# PA_MCU.net
KiCad netlist of a schematic drawn in Altium Designer
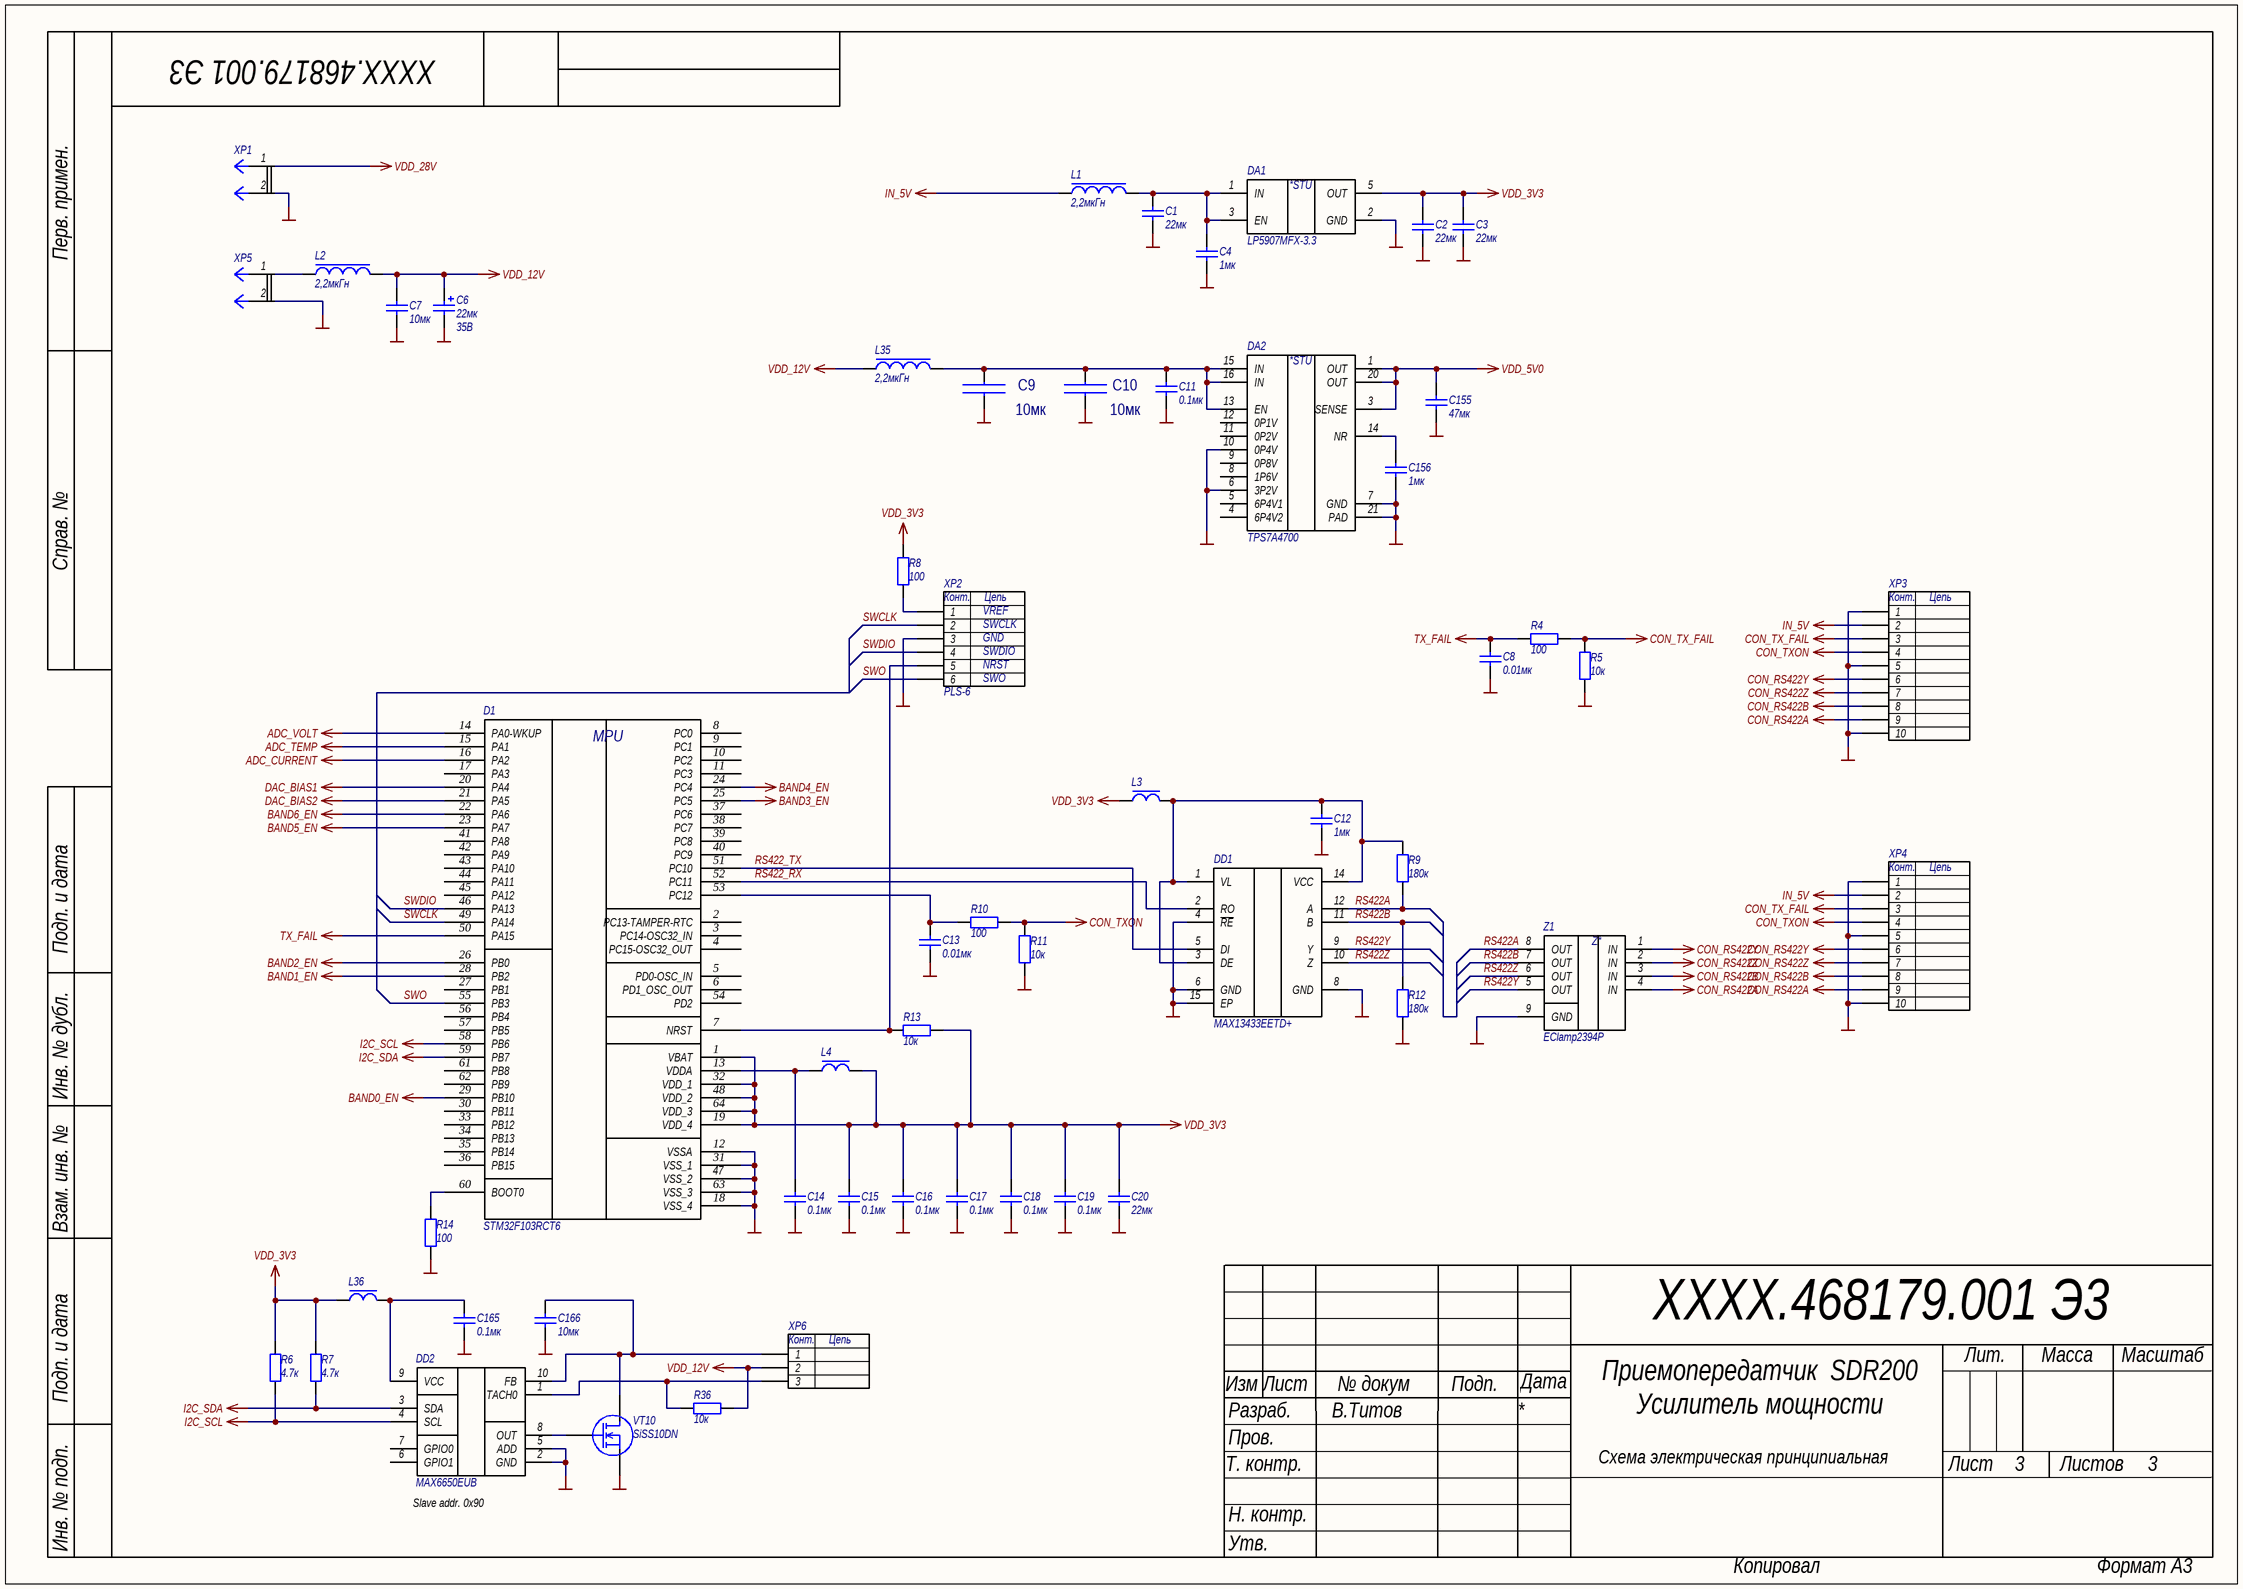
[diagram p0: PA_MCU.SchDoc]

(export (version "E")
  (design (tool "Eeschema 10.0.6"))
  (components
    (comp (ref "C1")
      (value "22мк")
      (footprint "CAPC2012X12L")
      (description "Кер. ЧИП-конденсатор")
      (fields (field (name "MANUFACTURER") "TDK") (field (name "TOLERANCE") "±10%"))
      (libsource (lib "nels_caps") (part "Кер.ЧИП конд. 0805 22мкФ X5R 10% 16В"))
    )
    (comp (ref "C2")
      (value "22мк")
      (footprint "CAPC2012X12L")
      (description "Кер. ЧИП-конденсатор")
      (fields (field (name "MANUFACTURER") "TDK") (field (name "TOLERANCE") "±10%"))
      (libsource (lib "nels_caps") (part "Кер.ЧИП конд. 0805 22мкФ X5R 10% 16В"))
    )
    (comp (ref "C3")
      (value "22мк")
      (footprint "CAPC2012X12L")
      (description "Кер. ЧИП-конденсатор")
      (fields (field (name "MANUFACTURER") "TDK") (field (name "TOLERANCE") "±10%"))
      (libsource (lib "nels_caps") (part "Кер.ЧИП конд. 0805 22мкФ X5R 10% 16В"))
    )
    (comp (ref "C4")
      (value "1мк")
      (footprint "CAPC1005X06N")
      (description "Кер. ЧИП-конденсатор")
      (fields (field (name "TOLERANCE") "±10%"))
      (libsource (lib "nels_caps") (part "Кер.ЧИП конд. 0402 1мкФ X5R 10%, 10В"))
    )
    (comp (ref "C6")
      (value "22мк")
      (footprint "CAPMP7343X28L")
      (description "Тант. ЧИП-конденсатор")
      (fields
        (field (name "TOLERANCE") "±20%")
        (field (name "POWER/VOLTAGE") "35В")
        (field (name "PUBLISHER") "Altium Limited")
      )
      (libsource (lib "nels_caps") (part "Конденсатор танталовый SMD D case 22мкФ ±20% 35B"))
    )
    (comp (ref "C7")
      (value "10мк")
      (footprint "CAPC3225X27L")
      (description "Кер. ЧИП-конденсатор")
      (fields (field (name "MANUFACTURER") "Murata") (field (name "TOLERANCE") "±20%"))
      (libsource (lib "nels_caps") (part "Кер.ЧИП конд. 1210 10мкФ X5R 20% 50В"))
    )
    (comp (ref "C8")
      (value "0.01мк")
      (footprint "CAPC1005X06N")
      (description "Кер. ЧИП-конденсатор")
      (fields (field (name "TOLERANCE") "±20%"))
      (libsource (lib "nels_caps") (part "Кер.ЧИП конд. 0402 0.01мкФ X7R 10%, 50В"))
    )
    (comp (ref "C9")
      (value "CC1206KKX7R8BB106")
      (footprint "CAPC3216X12L")
      (description "ЧИП конденсатор")
      (fields
        (field (name "MANUFACTURER") "Yageo")
        (field (name "TOLERANCE") "10%")
        (field (name "NOMINAL") "10мк")
      )
      (libsource (lib "Database_Gost") (part "Capacitor const"))
    )
    (comp (ref "C10")
      (value "CC0805KKX5R8BB106")
      (footprint "CAPC2012X09L")
      (description "ЧИП конденсатор")
      (fields
        (field (name "MANUFACTURER") "Yageo")
        (field (name "TOLERANCE") "0,1")
        (field (name "NOMINAL") "10мк")
      )
      (libsource (lib "Database_Gost") (part "Capacitor const"))
    )
    (comp (ref "C11")
      (value "0.1мк")
      (footprint "CAPC1005X06N")
      (description "Кер. ЧИП-конденсатор")
      (fields (field (name "TOLERANCE") "±10%"))
      (libsource (lib "nels") (part "Кер.ЧИП конд. 0402 0.1мкФ X7R 10%, 16В"))
    )
    (comp (ref "C12")
      (value "1мк")
      (footprint "CAPC1005X06N")
      (description "Кер. ЧИП-конденсатор")
      (fields (field (name "TOLERANCE") "±10%"))
      (libsource (lib "nels_caps") (part "Кер.ЧИП конд. 0402 1мкФ X5R 10%, 10В"))
    )
    (comp (ref "C13")
      (value "0.01мк")
      (footprint "CAPC1005X06N")
      (description "Кер. ЧИП-конденсатор")
      (fields (field (name "TOLERANCE") "±20%"))
      (libsource (lib "nels_caps") (part "Кер.ЧИП конд. 0402 0.01мкФ X7R 10%, 50В"))
    )
    (comp (ref "C14")
      (value "0.1мк")
      (footprint "CAPC1005X06N")
      (description "Кер. ЧИП-конденсатор")
      (fields (field (name "TOLERANCE") "±10%"))
      (libsource (lib "nels") (part "Кер.ЧИП конд. 0402 0.1мкФ X7R 10%, 16В"))
    )
    (comp (ref "C15")
      (value "0.1мк")
      (footprint "CAPC1005X06N")
      (description "Кер. ЧИП-конденсатор")
      (fields (field (name "TOLERANCE") "±10%"))
      (libsource (lib "nels") (part "Кер.ЧИП конд. 0402 0.1мкФ X7R 10%, 16В"))
    )
    (comp (ref "C16")
      (value "0.1мк")
      (footprint "CAPC1005X06N")
      (description "Кер. ЧИП-конденсатор")
      (fields (field (name "TOLERANCE") "±10%"))
      (libsource (lib "nels") (part "Кер.ЧИП конд. 0402 0.1мкФ X7R 10%, 16В"))
    )
    (comp (ref "C17")
      (value "0.1мк")
      (footprint "CAPC1005X06N")
      (description "Кер. ЧИП-конденсатор")
      (fields (field (name "TOLERANCE") "±10%"))
      (libsource (lib "nels") (part "Кер.ЧИП конд. 0402 0.1мкФ X7R 10%, 16В"))
    )
    (comp (ref "C18")
      (value "0.1мк")
      (footprint "CAPC1005X06N")
      (description "Кер. ЧИП-конденсатор")
      (fields (field (name "TOLERANCE") "±10%"))
      (libsource (lib "nels") (part "Кер.ЧИП конд. 0402 0.1мкФ X7R 10%, 16В"))
    )
    (comp (ref "C19")
      (value "0.1мк")
      (footprint "CAPC1005X06N")
      (description "Кер. ЧИП-конденсатор")
      (fields (field (name "TOLERANCE") "±10%"))
      (libsource (lib "nels") (part "Кер.ЧИП конд. 0402 0.1мкФ X7R 10%, 16В"))
    )
    (comp (ref "C20")
      (value "22мк")
      (footprint "CAPC2012X12L")
      (description "Кер. ЧИП-конденсатор")
      (fields (field (name "MANUFACTURER") "TDK") (field (name "TOLERANCE") "±10%"))
      (libsource (lib "nels_caps") (part "Кер.ЧИП конд. 0805 22мкФ X5R 10% 16В"))
    )
    (comp (ref "C155")
      (value "47мк")
      (footprint "CAPC2012X12L")
      (description "Кер. ЧИП-конденсатор")
      (fields (field (name "MANUFACTURER") "Murata") (field (name "TOLERANCE") "±20%"))
      (libsource (lib "nels_caps") (part "Кер.ЧИП конд. 0805 47мкФ X5R 20% 10В"))
    )
    (comp (ref "C156")
      (value "1мк")
      (footprint "CAPC1005X06N")
      (description "Кер. ЧИП-конденсатор")
      (fields (field (name "TOLERANCE") "±10%"))
      (libsource (lib "nels_caps") (part "Кер.ЧИП конд. 0402 1мкФ X5R 10%, 10В"))
    )
    (comp (ref "C165")
      (value "0.1мк")
      (footprint "CAPC1005X06N")
      (description "Кер. ЧИП-конденсатор")
      (fields (field (name "TOLERANCE") "±10%"))
      (libsource (lib "nels") (part "Кер.ЧИП конд. 0402 0.1мкФ X7R 10%, 16В"))
    )
    (comp (ref "C166")
      (value "10мк")
      (footprint "CAPC3225X27L")
      (description "Кер. ЧИП-конденсатор")
      (fields (field (name "MANUFACTURER") "Murata") (field (name "TOLERANCE") "±20%"))
      (libsource (lib "nels_caps") (part "Кер.ЧИП конд. 1210 10мкФ X5R 20% 50В"))
    )
    (comp (ref "D1")
      (value "STM32F103RCT6")
      (footprint "QFP50P1200X1200X160-64N")
      (fields (field (name "MANUFACTURER") "STMicroelectronics"))
      (libsource (lib "nels_chip") (part "Микросхема STM32F103RCT6"))
    )
    (comp (ref "DA1")
      (value "LP5907MFX-3.3")
      (footprint "SOT23-5AM")
      (description "250-mA Ultra-Low-Noise, Low-IQ LDO")
      (fields (field (name "MANUFACTURER") "TI"))
      (libsource (lib "nels_chip") (part "Микросхема LP5907MFX-3.3"))
    )
    (comp (ref "DA2")
      (value "TPS7A4700")
      (footprint "QFN65P500X500X100_HS-21L")
      (description "36-V, 1-A, 4-µVRMS, RF LDO Voltage Regulator")
      (fields (field (name "MANUFACTURER") "TI"))
      (libsource (lib "nels_chip") (part "Микросхема TPS7A4700RGW"))
    )
    (comp (ref "DD1")
      (value "MAX13433EETD+")
      (footprint "SON40P300X80_HS-15L")
      (description "RS-422 Transceivers with Low-Voltage Logic Interface 16M")
      (fields (field (name "MANUFACTURER") "Maxim"))
      (libsource (lib "nels_chip") (part "Микросхема MAX13433EETD+"))
    )
    (comp (ref "DD2")
      (value "MAX6650EUB")
      (footprint "SOP64P600X175-16N")
      (description "Fan-Speed Regulators and Monitors with SMBus/I2C-Compatible Interface")
      (fields (field (name "MANUFACTURER") "Maxim"))
      (libsource (lib "nels_chip") (part "Микросхема MAX6650EUB"))
    )
    (comp (ref "L1")
      (value "2,2мкГн")
      (footprint "CSAB0420")
      (description "Molding Power Choke")
      (fields
        (field (name "MANUFACTURER") "Vishay")
        (field (name "MANUFACTURERPARTNUMBER") "IHLP1616ABER1R0M11")
      )
      (libsource (lib "nels_ind") (part "ЧИП индуктивность CSAB0420-2R2M"))
    )
    (comp (ref "L2")
      (value "2,2мкГн")
      (footprint "CSAB0420")
      (description "Molding Power Choke")
      (fields
        (field (name "MANUFACTURER") "Vishay")
        (field (name "MANUFACTURERPARTNUMBER") "IHLP1616ABER1R0M11")
      )
      (libsource (lib "nels_ind") (part "ЧИП индуктивность CSAB0420-2R2M"))
    )
    (comp (ref "L3")
      (value "BLM18PG121SN1D")
      (footprint "INDC1608X08L")
      (description "SMD EMI Suppression Filter EMIFIL")
      (fields (field (name "MANUFACTURER") "Murata"))
      (libsource (lib "nels_ind") (part "ЧИП дроссель 0603 BLM18PG121SN1D"))
    )
    (comp (ref "L4")
      (value "BLM18PG121SN1D")
      (footprint "INDC1608X08L")
      (description "SMD EMI Suppression Filter EMIFIL")
      (fields (field (name "MANUFACTURER") "Murata"))
      (libsource (lib "nels_ind") (part "ЧИП дроссель 0603 BLM18PG121SN1D"))
    )
    (comp (ref "L35")
      (value "2,2мкГн")
      (footprint "CSAB0420")
      (description "Molding Power Choke")
      (fields
        (field (name "MANUFACTURER") "Vishay")
        (field (name "MANUFACTURERPARTNUMBER") "IHLP1616ABER1R0M11")
      )
      (libsource (lib "nels_ind") (part "ЧИП индуктивность CSAB0420-2R2M"))
    )
    (comp (ref "L36")
      (value "BLM18PG121SN1D")
      (footprint "INDC1608X08L")
      (description "SMD EMI Suppression Filter EMIFIL")
      (fields (field (name "MANUFACTURER") "Murata"))
      (libsource (lib "nels_ind") (part "ЧИП дроссель 0603 BLM18PG121SN1D"))
    )
    (comp (ref "R4")
      (value "100")
      (footprint "RESC1005X06N")
      (description "ЧИП-резистор")
      (fields (field (name "TOLERANCE") "±5%"))
      (libsource (lib "") (part "Чип резистор 0402 100 Ом, 5%_1"))
    )
    (comp (ref "R5")
      (value "10к")
      (footprint "RESC1005X06N")
      (description "ЧИП-резистор")
      (fields (field (name "TOLERANCE") "±5%"))
      (libsource (lib "") (part "Чип резистор 0402 10 кОм, 5%_1"))
    )
    (comp (ref "R6")
      (value "4.7к")
      (footprint "RESC1005X06N")
      (description "ЧИП-резистор")
      (fields (field (name "TOLERANCE") "±5%"))
      (libsource (lib "nels_res") (part "Чип резистор 0402 4,7 кОм, 5%"))
    )
    (comp (ref "R7")
      (value "4.7к")
      (footprint "RESC1005X06N")
      (description "ЧИП-резистор")
      (fields (field (name "TOLERANCE") "±5%"))
      (libsource (lib "nels_res") (part "Чип резистор 0402 4,7 кОм, 5%"))
    )
    (comp (ref "R8")
      (value "100")
      (footprint "RESC1005X06N")
      (description "ЧИП-резистор")
      (fields (field (name "TOLERANCE") "±5%"))
      (libsource (lib "nels_res") (part "Чип резистор 0402 100 Ом, 5%"))
    )
    (comp (ref "R9")
      (value "180к")
      (footprint "RESC1005X06N")
      (description "ЧИП-резистор")
      (fields (field (name "TOLERANCE") "±5%"))
      (libsource (lib "nels") (part "Чип резистор 0402 180 кОм, 5%"))
    )
    (comp (ref "R10")
      (value "100")
      (footprint "RESC1005X06N")
      (description "ЧИП-резистор")
      (fields (field (name "TOLERANCE") "±5%"))
      (libsource (lib "") (part "Чип резистор 0402 100 Ом, 5%_1"))
    )
    (comp (ref "R11")
      (value "10к")
      (footprint "RESC1005X06N")
      (description "ЧИП-резистор")
      (fields (field (name "TOLERANCE") "±5%"))
      (libsource (lib "") (part "Чип резистор 0402 10 кОм, 5%_1"))
    )
    (comp (ref "R12")
      (value "180к")
      (footprint "RESC1005X06N")
      (description "ЧИП-резистор")
      (fields (field (name "TOLERANCE") "±5%"))
      (libsource (lib "nels") (part "Чип резистор 0402 180 кОм, 5%"))
    )
    (comp (ref "R13")
      (value "10к")
      (footprint "RESC1005X06N")
      (description "ЧИП-резистор")
      (fields (field (name "TOLERANCE") "±5%"))
      (libsource (lib "nels_res") (part "Чип резистор 0402 10 кОм, 5%"))
    )
    (comp (ref "R14")
      (value "100")
      (footprint "RESC1005X06N")
      (description "ЧИП-резистор")
      (fields (field (name "TOLERANCE") "±5%"))
      (libsource (lib "nels_res") (part "Чип резистор 0402 100 Ом, 5%"))
    )
    (comp (ref "R36")
      (value "10к")
      (footprint "RESC1005X06N")
      (description "ЧИП-резистор")
      (fields (field (name "TOLERANCE") "±5%"))
      (libsource (lib "nels_res") (part "Чип резистор 0402 10 кОм, 5%"))
    )
    (comp (ref "VT10")
      (value "SiSS10DN")
      (footprint "PowerPAK_1212-8W")
      (description "N-Channel 40 V (D-S) MOSFET")
      (libsource (lib "nels_other") (part "ЧИП транзистор SiSS10DN"))
    )
    (comp (ref "XP1")
      (value "XT60-F")
      (footprint "XT60-F")
      (description "AMASS XT60-F")
      (libsource (lib "nels_conn") (part "Соединитель XT60-F"))
    )
    (comp (ref "XP2")
      (value "PLS-6")
      (footprint "HDR1X6")
      (description "Вилка штыревая 2.54мм 1x6 прямая тип1")
      (fields (field (name "PUBLISHER") "Altium Limited"))
      (libsource (lib "nels_conn") (part "Соединитель PLS-6"))
    )
    (comp (ref "XP3")
      (value "FH12-10S-0.5SVA")
      (footprint "FH12-10S-0.5SH")
      (description "0.5mm  Pitch FPC/FFC Connector FH12 Series")
      (fields (field (name "MANUFACTURER") "Hirose"))
      (libsource (lib "nels_conn") (part "Соединитель FH12-10S-0.5SVA"))
    )
    (comp (ref "XP4")
      (value "FH12-10S-0.5SVA")
      (footprint "FH12-10S-0.5SH")
      (description "0.5mm  Pitch FPC/FFC Connector FH12 Series")
      (fields (field (name "MANUFACTURER") "Hirose"))
      (libsource (lib "nels_conn") (part "Соединитель FH12-10S-0.5SVA"))
    )
    (comp (ref "XP5")
      (value "XT30UPB-M")
      (footprint "XT30UPB-M")
      (description "AMASS XT30UPB-M  5 mm")
      (libsource (lib "nels_conn") (part "Соединитель XT30UPB-M"))
    )
    (comp (ref "XP6")
      (value "22232031")
      (footprint "22232031")
      (description "Molex 2,54 мм pitch-3")
      (fields (field (name "MANUFACTURER") "Connfly"))
      (libsource (lib "nels_conn") (part "Соединитель 22232031"))
    )
    (comp (ref "Z1")
      (value "EClamp2394P")
      (footprint "SON50P160X65_HS-9N")
      (description "ESD/EMI Protection  for Color LCD Interfaces")
      (fields (field (name "MANUFACTURER") "SEMTECH"))
      (libsource (lib "nels_other") (part "Фильтр EMI EClamp2394P"))
    )
  )
  (nets
    (net (code "1") (name "/RS422A") (class "Default")
      (node (ref "DD1") (pin "12") (pinfunction "A_12") (pintype "passive"))
      (node (ref "R9") (pin "1") (pinfunction "1_1") (pintype "passive"))
      (node (ref "Z1") (pin "8") (pinfunction "OUT_8") (pintype "passive"))
    )
    (net (code "2") (name "/RS422B") (class "Default")
      (node (ref "DD1") (pin "11") (pinfunction "B_11") (pintype "passive"))
      (node (ref "R12") (pin "2") (pinfunction "2_2") (pintype "passive"))
      (node (ref "Z1") (pin "7") (pinfunction "OUT_7") (pintype "passive"))
    )
    (net (code "3") (name "/RS422Y") (class "Default")
      (node (ref "DD1") (pin "9") (pinfunction "Y_9") (pintype "passive"))
      (node (ref "Z1") (pin "5") (pinfunction "OUT_5") (pintype "passive"))
    )
    (net (code "4") (name "/RS422Z") (class "Default")
      (node (ref "DD1") (pin "10") (pinfunction "Z_10") (pintype "passive"))
      (node (ref "Z1") (pin "6") (pinfunction "OUT_6") (pintype "passive"))
    )
    (net (code "5") (name "/RS422_RX") (class "Default")
      (node (ref "D1") (pin "52") (pinfunction "PC11_52") (pintype "passive"))
      (node (ref "DD1") (pin "2") (pinfunction "RO_2") (pintype "passive"))
    )
    (net (code "6") (name "/RS422_TX") (class "Default")
      (node (ref "D1") (pin "51") (pinfunction "PC10_51") (pintype "passive"))
      (node (ref "DD1") (pin "5") (pinfunction "DI_5") (pintype "passive"))
    )
    (net (code "7") (name "/SWCLK") (class "Default")
      (node (ref "D1") (pin "49") (pinfunction "PA14_49") (pintype "passive"))
      (node (ref "XP2") (pin "2") (pinfunction "2_2") (pintype "passive"))
    )
    (net (code "8") (name "/SWDIO") (class "Default")
      (node (ref "D1") (pin "46") (pinfunction "PA13_46") (pintype "passive"))
      (node (ref "XP2") (pin "4") (pinfunction "4_4") (pintype "passive"))
    )
    (net (code "9") (name "/SWO") (class "Default")
      (node (ref "D1") (pin "55") (pinfunction "PB3_55") (pintype "passive"))
      (node (ref "XP2") (pin "6") (pinfunction "6_6") (pintype "passive"))
    )
    (net (code "10") (name "ADC_CURRENT") (class "Default")
      (node (ref "D1") (pin "16") (pinfunction "PA2_16") (pintype "passive"))
    )
    (net (code "11") (name "ADC_TEMP") (class "Default")
      (node (ref "D1") (pin "15") (pinfunction "PA1_15") (pintype "passive"))
    )
    (net (code "12") (name "ADC_VOLT") (class "Default")
      (node (ref "D1") (pin "14") (pinfunction "PA0-WKUP_14") (pintype "passive"))
    )
    (net (code "13") (name "BAND0_EN") (class "Default")
      (node (ref "D1") (pin "29") (pinfunction "PB10_29") (pintype "passive"))
    )
    (net (code "14") (name "BAND1_EN") (class "Default")
      (node (ref "D1") (pin "28") (pinfunction "PB2_28") (pintype "passive"))
    )
    (net (code "15") (name "BAND2_EN") (class "Default")
      (node (ref "D1") (pin "26") (pinfunction "PB0_26") (pintype "passive"))
    )
    (net (code "16") (name "BAND3_EN") (class "Default")
      (node (ref "D1") (pin "25") (pinfunction "PC5_25") (pintype "passive"))
    )
    (net (code "17") (name "BAND4_EN") (class "Default")
      (node (ref "D1") (pin "24") (pinfunction "PC4_24") (pintype "passive"))
    )
    (net (code "18") (name "BAND5_EN") (class "Default")
      (node (ref "D1") (pin "23") (pinfunction "PA7_23") (pintype "passive"))
    )
    (net (code "19") (name "BAND6_EN") (class "Default")
      (node (ref "D1") (pin "22") (pinfunction "PA6_22") (pintype "passive"))
    )
    (net (code "20") (name "CON_RS422A") (class "Default")
      (node (ref "XP3") (pin "9") (pinfunction "9_9") (pintype "passive"))
      (node (ref "XP4") (pin "9") (pinfunction "9_9") (pintype "passive"))
      (node (ref "Z1") (pin "4") (pinfunction "IN_4") (pintype "passive"))
    )
    (net (code "21") (name "CON_RS422B") (class "Default")
      (node (ref "XP3") (pin "8") (pinfunction "8_8") (pintype "passive"))
      (node (ref "XP4") (pin "8") (pinfunction "8_8") (pintype "passive"))
      (node (ref "Z1") (pin "3") (pinfunction "IN_3") (pintype "passive"))
    )
    (net (code "22") (name "CON_RS422Y") (class "Default")
      (node (ref "XP3") (pin "6") (pinfunction "6_6") (pintype "passive"))
      (node (ref "XP4") (pin "6") (pinfunction "6_6") (pintype "passive"))
      (node (ref "Z1") (pin "1") (pinfunction "IN_1") (pintype "passive"))
    )
    (net (code "23") (name "CON_RS422Z") (class "Default")
      (node (ref "XP3") (pin "7") (pinfunction "7_7") (pintype "passive"))
      (node (ref "XP4") (pin "7") (pinfunction "7_7") (pintype "passive"))
      (node (ref "Z1") (pin "2") (pinfunction "IN_2") (pintype "passive"))
    )
    (net (code "24") (name "CON_TXON") (class "Default")
      (node (ref "R10") (pin "1") (pinfunction "1_1") (pintype "passive"))
      (node (ref "R11") (pin "1") (pinfunction "1_1") (pintype "passive"))
      (node (ref "XP3") (pin "4") (pinfunction "4_4") (pintype "passive"))
      (node (ref "XP4") (pin "4") (pinfunction "4_4") (pintype "passive"))
    )
    (net (code "25") (name "CON_TX_FAIL") (class "Default")
      (node (ref "R4") (pin "1") (pinfunction "1_1") (pintype "passive"))
      (node (ref "R5") (pin "1") (pinfunction "1_1") (pintype "passive"))
      (node (ref "XP3") (pin "3") (pinfunction "3_3") (pintype "passive"))
      (node (ref "XP4") (pin "3") (pinfunction "3_3") (pintype "passive"))
    )
    (net (code "26") (name "DAC_BIAS1") (class "Default")
      (node (ref "D1") (pin "20") (pinfunction "PA4_20") (pintype "passive"))
    )
    (net (code "27") (name "DAC_BIAS2") (class "Default")
      (node (ref "D1") (pin "21") (pinfunction "PA5_21") (pintype "passive"))
    )
    (net (code "28") (name "GND") (class "Default")
      (node (ref "C1") (pin "1") (pinfunction "1_1") (pintype "passive"))
      (node (ref "C11") (pin "1") (pinfunction "1_1") (pintype "passive"))
      (node (ref "C12") (pin "1") (pinfunction "1_1") (pintype "passive"))
      (node (ref "C13") (pin "1") (pinfunction "1_1") (pintype "passive"))
      (node (ref "C14") (pin "1") (pinfunction "1_1") (pintype "passive"))
      (node (ref "C15") (pin "1") (pinfunction "1_1") (pintype "passive"))
      (node (ref "C155") (pin "1") (pinfunction "1_1") (pintype "passive"))
      (node (ref "C156") (pin "1") (pinfunction "1_1") (pintype "passive"))
      (node (ref "C16") (pin "1") (pinfunction "1_1") (pintype "passive"))
      (node (ref "C165") (pin "1") (pinfunction "1_1") (pintype "passive"))
      (node (ref "C166") (pin "1") (pinfunction "1_1") (pintype "passive"))
      (node (ref "C17") (pin "1") (pinfunction "1_1") (pintype "passive"))
      (node (ref "C18") (pin "1") (pinfunction "1_1") (pintype "passive"))
      (node (ref "C19") (pin "1") (pinfunction "1_1") (pintype "passive"))
      (node (ref "C2") (pin "1") (pinfunction "1_1") (pintype "passive"))
      (node (ref "C20") (pin "1") (pinfunction "1_1") (pintype "passive"))
      (node (ref "C3") (pin "1") (pinfunction "1_1") (pintype "passive"))
      (node (ref "C4") (pin "1") (pinfunction "1_1") (pintype "passive"))
      (node (ref "C6") (pin "1") (pinfunction "1_1") (pintype "passive"))
      (node (ref "C7") (pin "1") (pinfunction "1_1") (pintype "passive"))
      (node (ref "C8") (pin "1") (pinfunction "1_1") (pintype "passive"))
      (node (ref "D1") (pin "12") (pinfunction "VSSA_12") (pintype "passive"))
      (node (ref "D1") (pin "18") (pinfunction "VSS_4_18") (pintype "passive"))
      (node (ref "D1") (pin "31") (pinfunction "VSS_1_31") (pintype "passive"))
      (node (ref "D1") (pin "47") (pinfunction "VSS_2_47") (pintype "passive"))
      (node (ref "D1") (pin "63") (pinfunction "VSS_3_63") (pintype "passive"))
      (node (ref "DA1") (pin "2") (pinfunction "GND_2") (pintype "passive"))
      (node (ref "DA2") (pin "10") (pinfunction "0P4V_10") (pintype "passive"))
      (node (ref "DA2") (pin "21") (pinfunction "PAD_21") (pintype "passive"))
      (node (ref "DA2") (pin "6") (pinfunction "3P2V_6") (pintype "passive"))
      (node (ref "DA2") (pin "7") (pinfunction "GND_7") (pintype "passive"))
      (node (ref "DD1") (pin "15") (pinfunction "EP_15") (pintype "passive"))
      (node (ref "DD1") (pin "4") (pinfunction "~{RE}_4") (pintype "passive"))
      (node (ref "DD1") (pin "6") (pinfunction "GND_6") (pintype "passive"))
      (node (ref "DD1") (pin "8") (pinfunction "GND_8") (pintype "passive"))
      (node (ref "DD2") (pin "2") (pinfunction "GND_2") (pintype "passive"))
      (node (ref "DD2") (pin "5") (pinfunction "ADD_5") (pintype "passive"))
      (node (ref "R11") (pin "2") (pinfunction "2_2") (pintype "passive"))
      (node (ref "R12") (pin "1") (pinfunction "1_1") (pintype "passive"))
      (node (ref "R14") (pin "2") (pinfunction "2_2") (pintype "passive"))
      (node (ref "R5") (pin "2") (pinfunction "2_2") (pintype "passive"))
      (node (ref "VT10") (pin "S") (pinfunction "S_S") (pintype "passive"))
      (node (ref "XP1") (pin "2") (pinfunction "~_2") (pintype "passive"))
      (node (ref "XP2") (pin "3") (pinfunction "3_3") (pintype "passive"))
      (node (ref "XP3") (pin "1") (pinfunction "1_1") (pintype "passive"))
      (node (ref "XP3") (pin "10") (pinfunction "10_10") (pintype "passive"))
      (node (ref "XP3") (pin "5") (pinfunction "5_5") (pintype "passive"))
      (node (ref "XP4") (pin "1") (pinfunction "1_1") (pintype "passive"))
      (node (ref "XP4") (pin "10") (pinfunction "10_10") (pintype "passive"))
      (node (ref "XP4") (pin "5") (pinfunction "5_5") (pintype "passive"))
      (node (ref "XP5") (pin "2") (pinfunction "~_2") (pintype "passive"))
      (node (ref "Z1") (pin "9") (pinfunction "GND_9") (pintype "passive"))
    )
    (net (code "29") (name "I2C_SCL") (class "Default")
      (node (ref "D1") (pin "58") (pinfunction "PB6_58") (pintype "passive"))
      (node (ref "DD2") (pin "4") (pinfunction "SCL_4") (pintype "passive"))
      (node (ref "R6") (pin "1") (pinfunction "1_1") (pintype "passive"))
    )
    (net (code "30") (name "I2C_SDA") (class "Default")
      (node (ref "D1") (pin "59") (pinfunction "PB7_59") (pintype "passive"))
      (node (ref "DD2") (pin "3") (pinfunction "SDA_3") (pintype "passive"))
      (node (ref "R7") (pin "1") (pinfunction "1_1") (pintype "passive"))
    )
    (net (code "31") (name "IN_5V") (class "Default")
      (node (ref "L1") (pin "1") (pinfunction "1_1") (pintype "passive"))
      (node (ref "XP3") (pin "2") (pinfunction "2_2") (pintype "passive"))
      (node (ref "XP4") (pin "2") (pinfunction "2_2") (pintype "passive"))
    )
    (net (code "32") (name "Net-(D1-BOOT0)") (class "Default")
      (node (ref "D1") (pin "60") (pinfunction "BOOT0_60") (pintype "passive"))
      (node (ref "R14") (pin "1") (pinfunction "1_1") (pintype "passive"))
    )
    (net (code "33") (name "Net-(D1-NRST)") (class "Default")
      (node (ref "D1") (pin "7") (pinfunction "NRST_7") (pintype "passive"))
      (node (ref "R13") (pin "1") (pinfunction "1_1") (pintype "passive"))
      (node (ref "XP2") (pin "5") (pinfunction "5_5") (pintype "passive"))
    )
    (net (code "34") (name "Net-(D1-PC12)") (class "Default")
      (node (ref "C13") (pin "2") (pinfunction "2_2") (pintype "passive"))
      (node (ref "D1") (pin "53") (pinfunction "PC12_53") (pintype "passive"))
      (node (ref "R10") (pin "2") (pinfunction "2_2") (pintype "passive"))
    )
    (net (code "35") (name "Net-(D1-VDDA)") (class "Default")
      (node (ref "C14") (pin "2") (pinfunction "2_2") (pintype "passive"))
      (node (ref "D1") (pin "13") (pinfunction "VDDA_13") (pintype "passive"))
      (node (ref "L4") (pin "1") (pinfunction "1_1") (pintype "passive"))
    )
    (net (code "36") (name "Net-(DA1-EN)") (class "Default")
      (node (ref "C1") (pin "2") (pinfunction "2_2") (pintype "passive"))
      (node (ref "C4") (pin "2") (pinfunction "2_2") (pintype "passive"))
      (node (ref "DA1") (pin "1") (pinfunction "IN_1") (pintype "passive"))
      (node (ref "DA1") (pin "3") (pinfunction "EN_3") (pintype "passive"))
      (node (ref "L1") (pin "2") (pinfunction "2_2") (pintype "passive"))
    )
    (net (code "37") (name "Net-(DA2-EN)") (class "Default")
      (node (ref "C10") (pin "2") (pinfunction "2_2") (pintype "passive"))
      (node (ref "C11") (pin "2") (pinfunction "2_2") (pintype "passive"))
      (node (ref "C9") (pin "2") (pinfunction "2_2") (pintype "passive"))
      (node (ref "DA2") (pin "13") (pinfunction "EN_13") (pintype "passive"))
      (node (ref "DA2") (pin "15") (pinfunction "IN_15") (pintype "passive"))
      (node (ref "DA2") (pin "16") (pinfunction "IN_16") (pintype "passive"))
      (node (ref "L35") (pin "2") (pinfunction "2_2") (pintype "passive"))
    )
    (net (code "38") (name "Net-(DA2-NR)") (class "Default")
      (node (ref "C156") (pin "2") (pinfunction "2_2") (pintype "passive"))
      (node (ref "DA2") (pin "14") (pinfunction "NR_14") (pintype "passive"))
    )
    (net (code "39") (name "Net-(DD1-DE)") (class "Default")
      (node (ref "C12") (pin "2") (pinfunction "2_2") (pintype "passive"))
      (node (ref "DD1") (pin "1") (pinfunction "VL_1") (pintype "passive"))
      (node (ref "DD1") (pin "14") (pinfunction "VCC_14") (pintype "passive"))
      (node (ref "DD1") (pin "3") (pinfunction "DE_3") (pintype "passive"))
      (node (ref "L3") (pin "2") (pinfunction "2_2") (pintype "passive"))
      (node (ref "R9") (pin "2") (pinfunction "2_2") (pintype "passive"))
    )
    (net (code "40") (name "Net-(DD2-FB)") (class "Default")
      (node (ref "C166") (pin "2") (pinfunction "2_2") (pintype "passive"))
      (node (ref "DD2") (pin "10") (pinfunction "FB_10") (pintype "passive"))
      (node (ref "VT10") (pin "D") (pinfunction "D_D") (pintype "passive"))
      (node (ref "XP6") (pin "1") (pinfunction "1_1") (pintype "passive"))
    )
    (net (code "41") (name "Net-(DD2-OUT)") (class "Default")
      (node (ref "DD2") (pin "8") (pinfunction "OUT_8") (pintype "passive"))
      (node (ref "VT10") (pin "G") (pinfunction "G_G") (pintype "passive"))
    )
    (net (code "42") (name "Net-(DD2-TACH0)") (class "Default")
      (node (ref "DD2") (pin "1") (pinfunction "TACH0_1") (pintype "passive"))
      (node (ref "R36") (pin "1") (pinfunction "1_1") (pintype "passive"))
      (node (ref "XP6") (pin "3") (pinfunction "3_3") (pintype "passive"))
    )
    (net (code "43") (name "Net-(DD2-VCC)") (class "Default")
      (node (ref "C165") (pin "2") (pinfunction "2_2") (pintype "passive"))
      (node (ref "DD2") (pin "9") (pinfunction "VCC_9") (pintype "passive"))
      (node (ref "L36") (pin "2") (pinfunction "2_2") (pintype "passive"))
    )
    (net (code "44") (name "Net-(L2-Pad1)") (class "Default")
      (node (ref "L2") (pin "1") (pinfunction "1_1") (pintype "passive"))
      (node (ref "XP5") (pin "1") (pinfunction "~_1") (pintype "passive"))
    )
    (net (code "45") (name "Net-(R8-Pad2)") (class "Default")
      (node (ref "R8") (pin "2") (pinfunction "2_2") (pintype "passive"))
      (node (ref "XP2") (pin "1") (pinfunction "1_1") (pintype "passive"))
    )
    (net (code "46") (name "TX_FAIL") (class "Default")
      (node (ref "C8") (pin "2") (pinfunction "2_2") (pintype "passive"))
      (node (ref "D1") (pin "50") (pinfunction "PA15_50") (pintype "passive"))
      (node (ref "R4") (pin "2") (pinfunction "2_2") (pintype "passive"))
    )
    (net (code "47") (name "VDD_3V3") (class "Default")
      (node (ref "C15") (pin "2") (pinfunction "2_2") (pintype "passive"))
      (node (ref "C16") (pin "2") (pinfunction "2_2") (pintype "passive"))
      (node (ref "C17") (pin "2") (pinfunction "2_2") (pintype "passive"))
      (node (ref "C18") (pin "2") (pinfunction "2_2") (pintype "passive"))
      (node (ref "C19") (pin "2") (pinfunction "2_2") (pintype "passive"))
      (node (ref "C2") (pin "2") (pinfunction "2_2") (pintype "passive"))
      (node (ref "C20") (pin "2") (pinfunction "2_2") (pintype "passive"))
      (node (ref "C3") (pin "2") (pinfunction "2_2") (pintype "passive"))
      (node (ref "D1") (pin "1") (pinfunction "VBAT_1") (pintype "passive"))
      (node (ref "D1") (pin "19") (pinfunction "VDD_4_19") (pintype "passive"))
      (node (ref "D1") (pin "32") (pinfunction "VDD_1_32") (pintype "passive"))
      (node (ref "D1") (pin "48") (pinfunction "VDD_2_48") (pintype "passive"))
      (node (ref "D1") (pin "64") (pinfunction "VDD_3_64") (pintype "passive"))
      (node (ref "DA1") (pin "5") (pinfunction "OUT_5") (pintype "passive"))
      (node (ref "L3") (pin "1") (pinfunction "1_1") (pintype "passive"))
      (node (ref "L36") (pin "1") (pinfunction "1_1") (pintype "passive"))
      (node (ref "L4") (pin "2") (pinfunction "2_2") (pintype "passive"))
      (node (ref "R13") (pin "2") (pinfunction "2_2") (pintype "passive"))
      (node (ref "R6") (pin "2") (pinfunction "2_2") (pintype "passive"))
      (node (ref "R7") (pin "2") (pinfunction "2_2") (pintype "passive"))
      (node (ref "R8") (pin "1") (pinfunction "1_1") (pintype "passive"))
    )
    (net (code "48") (name "VDD_5V0") (class "Default")
      (node (ref "C155") (pin "2") (pinfunction "2_2") (pintype "passive"))
      (node (ref "DA2") (pin "1") (pinfunction "OUT_1") (pintype "passive"))
      (node (ref "DA2") (pin "20") (pinfunction "OUT_20") (pintype "passive"))
      (node (ref "DA2") (pin "3") (pinfunction "SENSE_3") (pintype "passive"))
    )
    (net (code "49") (name "VDD_12V") (class "Default")
      (node (ref "C6") (pin "2") (pinfunction "2_2") (pintype "passive"))
      (node (ref "C7") (pin "2") (pinfunction "2_2") (pintype "passive"))
      (node (ref "L2") (pin "2") (pinfunction "2_2") (pintype "passive"))
      (node (ref "L35") (pin "1") (pinfunction "1_1") (pintype "passive"))
      (node (ref "R36") (pin "2") (pinfunction "2_2") (pintype "passive"))
      (node (ref "XP6") (pin "2") (pinfunction "2_2") (pintype "passive"))
    )
    (net (code "50") (name "VDD_28V") (class "Default")
      (node (ref "XP1") (pin "1") (pinfunction "~_1") (pintype "passive"))
    )
    (net (code "51") (name "unconnected-(C9-Pad1)") (class "Default")
      (node (ref "C9") (pin "1") (pinfunction "1_1") (pintype "passive"))
    )
    (net (code "52") (name "unconnected-(C10-Pad1)") (class "Default")
      (node (ref "C10") (pin "1") (pinfunction "1_1") (pintype "passive"))
    )
    (net (code "53") (name "unconnected-(D1-PA3-Pad17)") (class "Default")
      (node (ref "D1") (pin "17") (pinfunction "PA3_17") (pintype "passive"))
    )
    (net (code "54") (name "unconnected-(D1-PA8-Pad41)") (class "Default")
      (node (ref "D1") (pin "41") (pinfunction "PA8_41") (pintype "passive"))
    )
    (net (code "55") (name "unconnected-(D1-PA9-Pad42)") (class "Default")
      (node (ref "D1") (pin "42") (pinfunction "PA9_42") (pintype "passive"))
    )
    (net (code "56") (name "unconnected-(D1-PA10-Pad43)") (class "Default")
      (node (ref "D1") (pin "43") (pinfunction "PA10_43") (pintype "passive"))
    )
    (net (code "57") (name "unconnected-(D1-PA11-Pad44)") (class "Default")
      (node (ref "D1") (pin "44") (pinfunction "PA11_44") (pintype "passive"))
    )
    (net (code "58") (name "unconnected-(D1-PA12-Pad45)") (class "Default")
      (node (ref "D1") (pin "45") (pinfunction "PA12_45") (pintype "passive"))
    )
    (net (code "59") (name "unconnected-(D1-PB1-Pad27)") (class "Default")
      (node (ref "D1") (pin "27") (pinfunction "PB1_27") (pintype "passive"))
    )
    (net (code "60") (name "unconnected-(D1-PB4-Pad56)") (class "Default")
      (node (ref "D1") (pin "56") (pinfunction "PB4_56") (pintype "passive"))
    )
    (net (code "61") (name "unconnected-(D1-PB5-Pad57)") (class "Default")
      (node (ref "D1") (pin "57") (pinfunction "PB5_57") (pintype "passive"))
    )
    (net (code "62") (name "unconnected-(D1-PB8-Pad61)") (class "Default")
      (node (ref "D1") (pin "61") (pinfunction "PB8_61") (pintype "passive"))
    )
    (net (code "63") (name "unconnected-(D1-PB9-Pad62)") (class "Default")
      (node (ref "D1") (pin "62") (pinfunction "PB9_62") (pintype "passive"))
    )
    (net (code "64") (name "unconnected-(D1-PB11-Pad30)") (class "Default")
      (node (ref "D1") (pin "30") (pinfunction "PB11_30") (pintype "passive"))
    )
    (net (code "65") (name "unconnected-(D1-PB12-Pad33)") (class "Default")
      (node (ref "D1") (pin "33") (pinfunction "PB12_33") (pintype "passive"))
    )
    (net (code "66") (name "unconnected-(D1-PB13-Pad34)") (class "Default")
      (node (ref "D1") (pin "34") (pinfunction "PB13_34") (pintype "passive"))
    )
    (net (code "67") (name "unconnected-(D1-PB14-Pad35)") (class "Default")
      (node (ref "D1") (pin "35") (pinfunction "PB14_35") (pintype "passive"))
    )
    (net (code "68") (name "unconnected-(D1-PB15-Pad36)") (class "Default")
      (node (ref "D1") (pin "36") (pinfunction "PB15_36") (pintype "passive"))
    )
    (net (code "69") (name "unconnected-(D1-PC0-Pad8)") (class "Default")
      (node (ref "D1") (pin "8") (pinfunction "PC0_8") (pintype "passive"))
    )
    (net (code "70") (name "unconnected-(D1-PC1-Pad9)") (class "Default")
      (node (ref "D1") (pin "9") (pinfunction "PC1_9") (pintype "passive"))
    )
    (net (code "71") (name "unconnected-(D1-PC2-Pad10)") (class "Default")
      (node (ref "D1") (pin "10") (pinfunction "PC2_10") (pintype "passive"))
    )
    (net (code "72") (name "unconnected-(D1-PC3-Pad11)") (class "Default")
      (node (ref "D1") (pin "11") (pinfunction "PC3_11") (pintype "passive"))
    )
    (net (code "73") (name "unconnected-(D1-PC6-Pad37)") (class "Default")
      (node (ref "D1") (pin "37") (pinfunction "PC6_37") (pintype "passive"))
    )
    (net (code "74") (name "unconnected-(D1-PC7-Pad38)") (class "Default")
      (node (ref "D1") (pin "38") (pinfunction "PC7_38") (pintype "passive"))
    )
    (net (code "75") (name "unconnected-(D1-PC8-Pad39)") (class "Default")
      (node (ref "D1") (pin "39") (pinfunction "PC8_39") (pintype "passive"))
    )
    (net (code "76") (name "unconnected-(D1-PC9-Pad40)") (class "Default")
      (node (ref "D1") (pin "40") (pinfunction "PC9_40") (pintype "passive"))
    )
    (net (code "77") (name "unconnected-(D1-PC13-TAMPER-RTC-Pad2)") (class "Default")
      (node (ref "D1") (pin "2") (pinfunction "PC13-TAMPER-RTC_2") (pintype "passive"))
    )
    (net (code "78") (name "unconnected-(D1-PC14-OSC32_IN-Pad3)") (class "Default")
      (node (ref "D1") (pin "3") (pinfunction "PC14-OSC32_IN_3") (pintype "passive"))
    )
    (net (code "79") (name "unconnected-(D1-PC15-OSC32_OUT-Pad4)") (class "Default")
      (node (ref "D1") (pin "4") (pinfunction "PC15-OSC32_OUT_4") (pintype "passive"))
    )
    (net (code "80") (name "unconnected-(D1-PD0-OSC_IN-Pad5)") (class "Default")
      (node (ref "D1") (pin "5") (pinfunction "PD0-OSC_IN_5") (pintype "passive"))
    )
    (net (code "81") (name "unconnected-(D1-PD1_OSC_OUT-Pad6)") (class "Default")
      (node (ref "D1") (pin "6") (pinfunction "PD1_OSC_OUT_6") (pintype "passive"))
    )
    (net (code "82") (name "unconnected-(D1-PD2-Pad54)") (class "Default")
      (node (ref "D1") (pin "54") (pinfunction "PD2_54") (pintype "passive"))
    )
    (net (code "83") (name "unconnected-(DA2-0P1V-Pad12)") (class "Default")
      (node (ref "DA2") (pin "12") (pinfunction "0P1V_12") (pintype "passive"))
    )
    (net (code "84") (name "unconnected-(DA2-0P2V-Pad11)") (class "Default")
      (node (ref "DA2") (pin "11") (pinfunction "0P2V_11") (pintype "passive"))
    )
    (net (code "85") (name "unconnected-(DA2-0P8V-Pad9)") (class "Default")
      (node (ref "DA2") (pin "9") (pinfunction "0P8V_9") (pintype "passive"))
    )
    (net (code "86") (name "unconnected-(DA2-1P6V-Pad8)") (class "Default")
      (node (ref "DA2") (pin "8") (pinfunction "1P6V_8") (pintype "passive"))
    )
    (net (code "87") (name "unconnected-(DA2-6P4V1-Pad5)") (class "Default")
      (node (ref "DA2") (pin "5") (pinfunction "6P4V1_5") (pintype "passive"))
    )
    (net (code "88") (name "unconnected-(DA2-6P4V2-Pad4)") (class "Default")
      (node (ref "DA2") (pin "4") (pinfunction "6P4V2_4") (pintype "passive"))
    )
    (net (code "89") (name "unconnected-(DD2-GPIO0-Pad7)") (class "Default")
      (node (ref "DD2") (pin "7") (pinfunction "GPIO0_7") (pintype "passive"))
    )
    (net (code "90") (name "unconnected-(DD2-GPIO1-Pad6)") (class "Default")
      (node (ref "DD2") (pin "6") (pinfunction "GPIO1_6") (pintype "passive"))
    )
  )
)
